# mcu_valdis2.net
KiCad netlist of a schematic drawn in Altium Designer
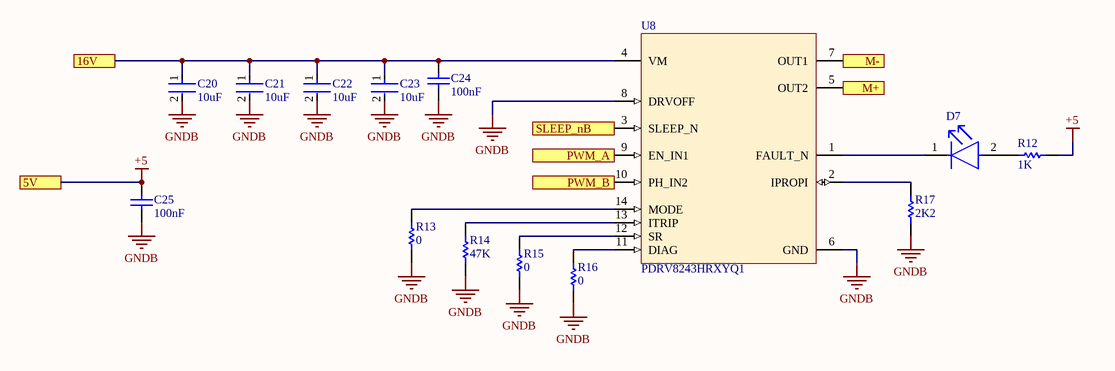
[diagram p0: mcu_valdis2.SchDoc]

(export (version "E")
  (design (tool "Eeschema 10.0.6"))
  (components
    (comp (ref "C20")
      (value "10uF")
      (footprint "FP-CL21-IPC_C")
      (description "CL21 Series 0805 22uF 25V ±20% Tolerance X5R Multilayer Ceramic Chip Capacitor")
      (libsource (lib "Altium Content Vault") (part "b4654b650e69147ec39a6b967a45e02"))
    )
    (comp (ref "C21")
      (value "10uF")
      (footprint "FP-CL21-IPC_C")
      (description "CL21 Series 0805 22uF 25V ±20% Tolerance X5R Multilayer Ceramic Chip Capacitor")
      (libsource (lib "Altium Content Vault") (part "b4654b650e69147ec39a6b967a45e02"))
    )
    (comp (ref "C22")
      (value "10uF")
      (footprint "FP-CL21-IPC_C")
      (description "CL21 Series 0805 22uF 25V ±20% Tolerance X5R Multilayer Ceramic Chip Capacitor")
      (libsource (lib "Altium Content Vault") (part "b4654b650e69147ec39a6b967a45e02"))
    )
    (comp (ref "C23")
      (value "10uF")
      (footprint "FP-CL21-IPC_C")
      (description "CL21 Series 0805 22uF 25V ±20% Tolerance X5R Multilayer Ceramic Chip Capacitor")
      (libsource (lib "Altium Content Vault") (part "b4654b650e69147ec39a6b967a45e02"))
    )
    (comp (ref "C24")
      (value "100nF")
      (footprint "CAPC1608X90X35ML10T15")
      (description "Chip Capacitor, 22 pF, +/- 5%, 50 V, -55 to 125 degC, 0603 (1608 Metric), RoHS, Tape and Reel")
      (fields (field (name "MANUFACTURER") "Murata"))
      (libsource (lib "Altium Content Vault") (part "CAP-NP-2"))
    )
    (comp (ref "C25")
      (value "100nF")
      (footprint "CAPC1608X90X35ML10T15")
      (description "Chip Capacitor, 22 pF, +/- 5%, 50 V, -55 to 125 degC, 0603 (1608 Metric), RoHS, Tape and Reel")
      (fields (field (name "MANUFACTURER") "Murata"))
      (libsource (lib "Altium Content Vault") (part "CAP-NP-2"))
    )
    (comp (ref "D7")
      (value "LTST-C191TBKT")
      (footprint "FP-LTST-C191TBKT-MFG")
      (description "LED BLUE CLEAR CHIP SMD")
      (libsource (lib "Altium Content Vault") (part "8706943c75ba83719d021d2fdc84c58"))
    )
    (comp (ref "R12")
      (value "1K")
      (footprint "RESC1609X50X30NL8T20")
      (description "Chip Resistor, 0 Ohm, Jumper, 100 mW, -55 to 155 degC, 0603 (1608 Metric), RoHS, Tape and Reel")
      (fields (field (name "MANUFACTURER") "Vishay Semiconductor"))
      (libsource (lib "Altium Content Vault") (part "RES-2"))
    )
    (comp (ref "R13")
      (value "0")
      (footprint "RESC1609X50X30NL8T20")
      (description "Chip Resistor, 0 Ohm, Jumper, 100 mW, -55 to 155 degC, 0603 (1608 Metric), RoHS, Tape and Reel")
      (fields (field (name "MANUFACTURER") "Vishay Semiconductor"))
      (libsource (lib "Altium Content Vault") (part "RES-2"))
    )
    (comp (ref "R14")
      (value "47K")
      (footprint "RESC1609X50X30NL8T20")
      (description "Chip Resistor, 0 Ohm, Jumper, 100 mW, -55 to 155 degC, 0603 (1608 Metric), RoHS, Tape and Reel")
      (fields (field (name "MANUFACTURER") "Vishay Semiconductor"))
      (libsource (lib "Altium Content Vault") (part "RES-2"))
    )
    (comp (ref "R15")
      (value "0")
      (footprint "RESC1609X50X30NL8T20")
      (description "Chip Resistor, 0 Ohm, Jumper, 100 mW, -55 to 155 degC, 0603 (1608 Metric), RoHS, Tape and Reel")
      (fields (field (name "MANUFACTURER") "Vishay Semiconductor"))
      (libsource (lib "Altium Content Vault") (part "RES-2"))
    )
    (comp (ref "R16")
      (value "0")
      (footprint "RESC1609X50X30NL8T20")
      (description "Chip Resistor, 0 Ohm, Jumper, 100 mW, -55 to 155 degC, 0603 (1608 Metric), RoHS, Tape and Reel")
      (fields (field (name "MANUFACTURER") "Vishay Semiconductor"))
      (libsource (lib "Altium Content Vault") (part "RES-2"))
    )
    (comp (ref "R17")
      (value "2K2")
      (footprint "RESC1609X50X30NL8T20")
      (description "Chip Resistor, 0 Ohm, Jumper, 100 mW, -55 to 155 degC, 0603 (1608 Metric), RoHS, Tape and Reel")
      (fields (field (name "MANUFACTURER") "Vishay Semiconductor"))
      (libsource (lib "Altium Content Vault") (part "RES-2"))
    )
    (comp (ref "U8")
      (value "PDRV8243HRXYQ1")
      (footprint "RXY0014A-MFG")
      (description "No Description Available")
      (fields (field (name "COPYRIGHT") "Copyright (C) 2022 Ultra Librarian. All rights reserved."))
      (libsource (lib "Valdis_Components") (part "PDRV8243HRXYQ1"))
    )
  )
  (nets
    (net (code "1") (name "+5") (class "Default")
      (node (ref "C25") (pin "2") (pinfunction "2_2") (pintype "passive"))
      (node (ref "R12") (pin "2") (pinfunction "2_2") (pintype "passive"))
    )
    (net (code "2") (name "/16V") (class "Default")
      (node (ref "C20") (pin "1") (pinfunction "1_1") (pintype "passive"))
      (node (ref "C21") (pin "1") (pinfunction "1_1") (pintype "passive"))
      (node (ref "C22") (pin "1") (pinfunction "1_1") (pintype "passive"))
      (node (ref "C23") (pin "1") (pinfunction "1_1") (pintype "passive"))
      (node (ref "C24") (pin "2") (pinfunction "2_2") (pintype "passive"))
      (node (ref "U8") (pin "4") (pinfunction "VM_4") (pintype "power_in"))
    )
    (net (code "3") (name "/M+") (class "Default")
      (node (ref "U8") (pin "5") (pinfunction "OUT2_5") (pintype "passive"))
    )
    (net (code "4") (name "/M-") (class "Default")
      (node (ref "U8") (pin "7") (pinfunction "OUT1_7") (pintype "passive"))
    )
    (net (code "5") (name "/PWM_A") (class "Default")
      (node (ref "U8") (pin "9") (pinfunction "EN_IN1_9") (pintype "input"))
    )
    (net (code "6") (name "/PWM_B") (class "Default")
      (node (ref "U8") (pin "10") (pinfunction "PH_IN2_10") (pintype "input"))
    )
    (net (code "7") (name "/SLEEP_nB") (class "Default")
      (node (ref "U8") (pin "3") (pinfunction "SLEEP_N_3") (pintype "input"))
    )
    (net (code "8") (name "GNDB") (class "Default")
      (node (ref "C20") (pin "2") (pinfunction "2_2") (pintype "passive"))
      (node (ref "C21") (pin "2") (pinfunction "2_2") (pintype "passive"))
      (node (ref "C22") (pin "2") (pinfunction "2_2") (pintype "passive"))
      (node (ref "C23") (pin "2") (pinfunction "2_2") (pintype "passive"))
      (node (ref "C24") (pin "1") (pinfunction "1_1") (pintype "passive"))
      (node (ref "C25") (pin "1") (pinfunction "1_1") (pintype "passive"))
      (node (ref "R13") (pin "1") (pinfunction "1_1") (pintype "passive"))
      (node (ref "R14") (pin "1") (pinfunction "1_1") (pintype "passive"))
      (node (ref "R15") (pin "1") (pinfunction "1_1") (pintype "passive"))
      (node (ref "R16") (pin "1") (pinfunction "1_1") (pintype "passive"))
      (node (ref "R17") (pin "1") (pinfunction "1_1") (pintype "passive"))
      (node (ref "U8") (pin "6") (pinfunction "GND_6") (pintype "power_in"))
      (node (ref "U8") (pin "8") (pinfunction "DRVOFF_8") (pintype "input"))
    )
    (net (code "9") (name "Net-(D7-A)") (class "Default")
      (node (ref "D7") (pin "2") (pinfunction "A_2") (pintype "passive"))
      (node (ref "R12") (pin "1") (pinfunction "1_1") (pintype "passive"))
    )
    (net (code "10") (name "Net-(D7-C)") (class "Default")
      (node (ref "D7") (pin "1") (pinfunction "C_1") (pintype "passive"))
      (node (ref "U8") (pin "1") (pinfunction "FAULT_N_1") (pintype "open_collector"))
    )
    (net (code "11") (name "Net-(U8-DIAG)") (class "Default")
      (node (ref "R16") (pin "2") (pinfunction "2_2") (pintype "passive"))
      (node (ref "U8") (pin "11") (pinfunction "DIAG_11") (pintype "input"))
    )
    (net (code "12") (name "Net-(U8-IPROPI)") (class "Default")
      (node (ref "R17") (pin "2") (pinfunction "2_2") (pintype "passive"))
      (node (ref "U8") (pin "2") (pinfunction "IPROPI_2") (pintype "bidirectional"))
    )
    (net (code "13") (name "Net-(U8-ITRIP)") (class "Default")
      (node (ref "R14") (pin "2") (pinfunction "2_2") (pintype "passive"))
      (node (ref "U8") (pin "13") (pinfunction "ITRIP_13") (pintype "input"))
    )
    (net (code "14") (name "Net-(U8-MODE)") (class "Default")
      (node (ref "R13") (pin "2") (pinfunction "2_2") (pintype "passive"))
      (node (ref "U8") (pin "14") (pinfunction "MODE_14") (pintype "input"))
    )
    (net (code "15") (name "Net-(U8-SR)") (class "Default")
      (node (ref "R15") (pin "2") (pinfunction "2_2") (pintype "passive"))
      (node (ref "U8") (pin "12") (pinfunction "SR_12") (pintype "input"))
    )
  )
)
